# Motortreiber_5_6.net
KiCad netlist of a schematic drawn in Altium Designer
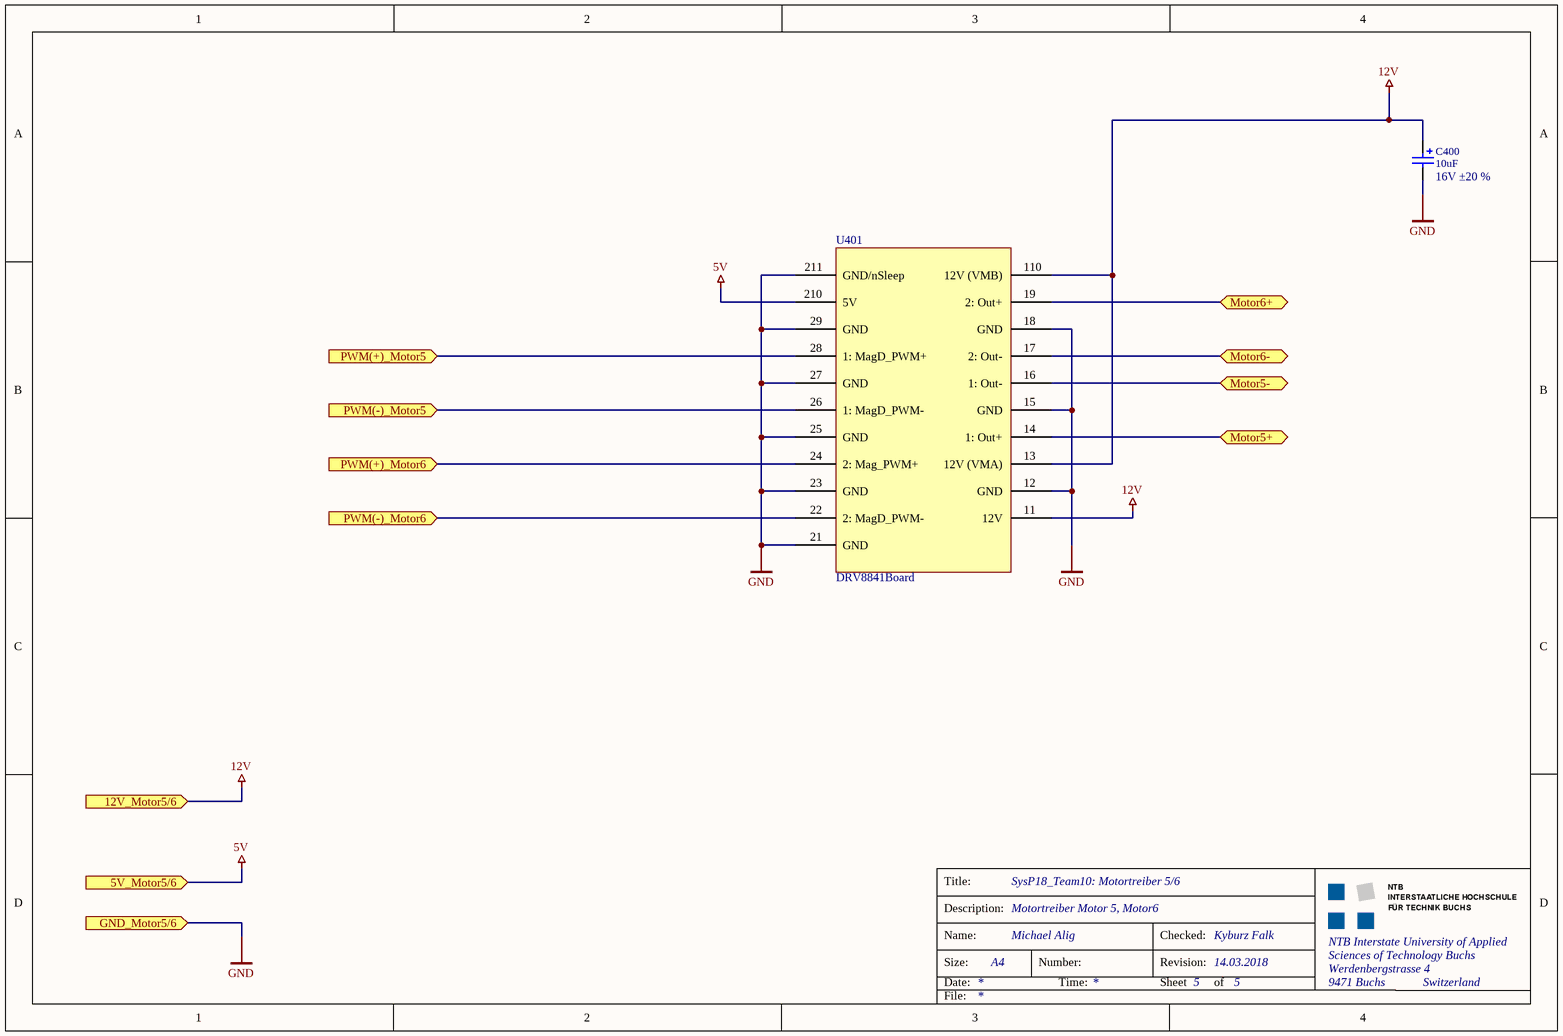
[diagram p0: Motortreiber_5,6.SchDoc]

(export (version "E")
  (design (tool "Eeschema 10.0.6"))
  (components
    (comp (ref "C400")
      (value "10uF")
      (footprint "CDE_CAP AVE CODE D_H")
      (description "Aluminum Electrolytic Capacitors for Filtering and Bypass, 47uF, 16V")
      (fields
        (field (name "MANUFACTURER") "Cornell Dubilier")
        (field (name "VALUEADDON") "16V ±20 %")
        (field (name "Comment") "AVE476M16D16T-F")
        (field (name "PUBLISHER") "Stefan Ursella, M.Eng")
      )
      (libsource (lib "Motorentreiber") (part "CDE_AVE476M16D16T-F_AVE CODE D"))
    )
    (comp (ref "U401")
      (value "DRV8841Board")
      (footprint "DRV8841_Board")
      (libsource (lib "Motorentreiber") (part "DRV8841_Board"))
    )
  )
  (nets
    (net (code "1") (name "/Motor5+") (class "Default")
      (node (ref "U401") (pin "14") (pinfunction "1:_Out+_14") (pintype "passive"))
    )
    (net (code "2") (name "/Motor5-") (class "Default")
      (node (ref "U401") (pin "16") (pinfunction "1:_Out-_16") (pintype "passive"))
    )
    (net (code "3") (name "/Motor6+") (class "Default")
      (node (ref "U401") (pin "19") (pinfunction "2:_Out+_19") (pintype "passive"))
    )
    (net (code "4") (name "/Motor6-") (class "Default")
      (node (ref "U401") (pin "17") (pinfunction "2:_Out-_17") (pintype "passive"))
    )
    (net (code "5") (name "/PWM(+)_Motor5") (class "Default")
      (node (ref "U401") (pin "28") (pinfunction "1:_MagD_PWM+_28") (pintype "passive"))
    )
    (net (code "6") (name "/PWM(+)_Motor6") (class "Default")
      (node (ref "U401") (pin "24") (pinfunction "2:_Mag_PWM+_24") (pintype "passive"))
    )
    (net (code "7") (name "/PWM(-)_Motor5") (class "Default")
      (node (ref "U401") (pin "26") (pinfunction "1:_MagD_PWM-_26") (pintype "passive"))
    )
    (net (code "8") (name "/PWM(-)_Motor6") (class "Default")
      (node (ref "U401") (pin "22") (pinfunction "2:_MagD_PWM-_22") (pintype "passive"))
    )
    (net (code "9") (name "5V") (class "Default")
      (node (ref "U401") (pin "210") (pinfunction "5V_210") (pintype "passive"))
    )
    (net (code "10") (name "12V") (class "Default")
      (node (ref "C400") (pin "1") (pinfunction "Pos_1") (pintype "passive"))
      (node (ref "U401") (pin "11") (pinfunction "12V_11") (pintype "passive"))
      (node (ref "U401") (pin "110") (pinfunction "12V_(VMB)_110") (pintype "passive"))
      (node (ref "U401") (pin "13") (pinfunction "12V_(VMA)_13") (pintype "passive"))
    )
    (net (code "11") (name "GND") (class "Default")
      (node (ref "C400") (pin "2") (pinfunction "Neg_2") (pintype "passive"))
      (node (ref "U401") (pin "12") (pinfunction "GND_12") (pintype "passive"))
      (node (ref "U401") (pin "15") (pinfunction "GND_15") (pintype "passive"))
      (node (ref "U401") (pin "18") (pinfunction "GND_18") (pintype "passive"))
      (node (ref "U401") (pin "21") (pinfunction "GND_21") (pintype "passive"))
      (node (ref "U401") (pin "211") (pinfunction "GND/nSleep_211") (pintype "passive"))
      (node (ref "U401") (pin "23") (pinfunction "GND_23") (pintype "passive"))
      (node (ref "U401") (pin "25") (pinfunction "GND_25") (pintype "passive"))
      (node (ref "U401") (pin "27") (pinfunction "GND_27") (pintype "passive"))
      (node (ref "U401") (pin "29") (pinfunction "GND_29") (pintype "passive"))
    )
  )
)
